# pressure-humidity-main.net
KiCad netlist of a schematic drawn in EAGLE
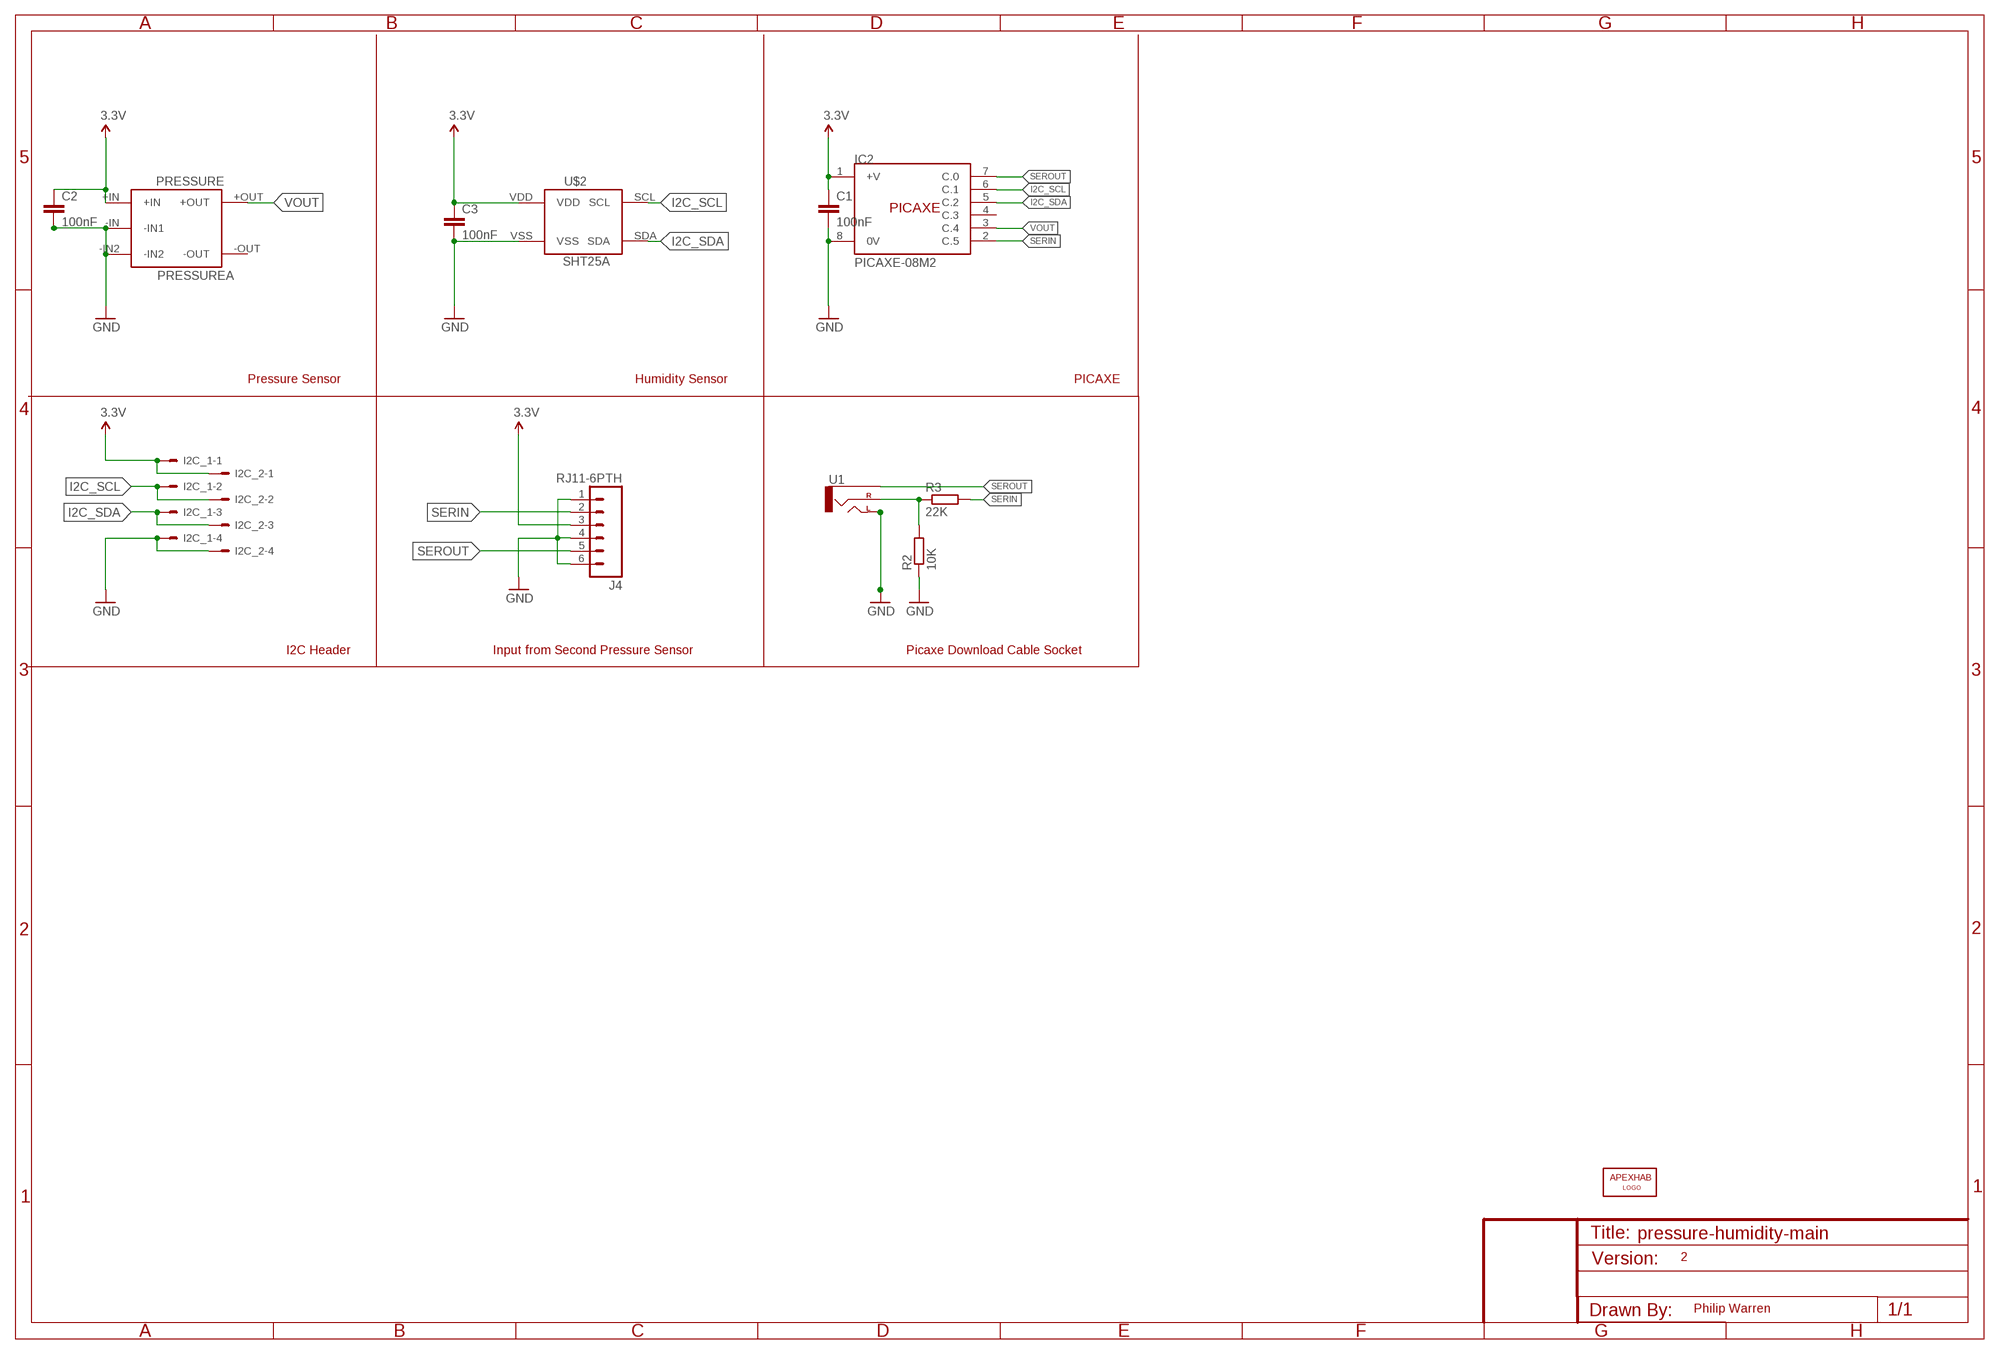
[diagram p0: schematic, sheet 1]

(export (version "E")
  (design (tool "Eeschema 10.0.6"))
  (components
    (comp (ref "C1")
      (value "100nF")
      (footprint "eagle-import:0805")
      (libsource (lib "eagle-import") (part "CAP0805"))
    )
    (comp (ref "C2")
      (value "100nF")
      (footprint "eagle-import:0805")
      (libsource (lib "eagle-import") (part "CAP0805"))
    )
    (comp (ref "C3")
      (value "100nF")
      (footprint "eagle-import:0805")
      (libsource (lib "eagle-import") (part "CAP0805"))
    )
    (comp (ref "I2C_1")
      (value "22-27-2041-04")
      (footprint "eagle-import:6410-04")
      (libsource (lib "eagle-import") (part "22-?-0427-2041"))
    )
    (comp (ref "I2C_2")
      (value "22-27-2041-04")
      (footprint "eagle-import:6410-04")
      (libsource (lib "eagle-import") (part "22-?-0427-2041"))
    )
    (comp (ref "IC2")
      (value "PICAXE-08M2")
      (footprint "eagle-import:SOIC8")
      (libsource (lib "eagle-import") (part "PICAXE-08M2"))
    )
    (comp (ref "J4")
      (value "RJ11-6PTH")
      (footprint "eagle-import:RJ11-6")
      (libsource (lib "eagle-import") (part "RJ11-6PTH"))
    )
    (comp (ref "JP1")
      (value "APEXHAB-LOGO_APEXHAB-SMALL")
      (footprint "eagle-import:APEXHAB-LOGO-SMALL")
      (libsource (lib "eagle-import") (part "APEXHAB-LOGO_APEXHAB-SMALL"))
    )
    (comp (ref "PRESSURE")
      (value "PRESSUREA")
      (footprint "eagle-import:PRESSURE")
      (libsource (lib "eagle-import") (part "PRESSUREA"))
    )
    (comp (ref "R2")
      (value "10K")
      (footprint "eagle-import:R0805")
      (libsource (lib "eagle-import") (part "R-EU_R0805"))
    )
    (comp (ref "R3")
      (value "22K")
      (footprint "eagle-import:R0805")
      (libsource (lib "eagle-import") (part "R-EU_R0805"))
    )
    (comp (ref "U$2")
      (value "SHT25A")
      (footprint "eagle-import:SHT25")
      (libsource (lib "eagle-import") (part "SHT25A"))
    )
    (comp (ref "U1")
      (value "AUDIO-JACKPTH")
      (footprint "eagle-import:AUDIO-JACK")
      (libsource (lib "eagle-import") (part "AUDIO-JACKPTH"))
    )
  )
  (nets
    (net (code "1") (name "3.3V") (class "Default")
      (node (ref "C1") (pin "1") (pinfunction "1_1") (pintype "passive"))
      (node (ref "C2") (pin "1") (pinfunction "1_1") (pintype "passive"))
      (node (ref "C3") (pin "1") (pinfunction "1_1") (pintype "passive"))
      (node (ref "I2C_1") (pin "1") (pinfunction "S_1") (pintype "passive"))
      (node (ref "I2C_2") (pin "1") (pinfunction "S_1") (pintype "passive"))
      (node (ref "IC2") (pin "1") (pinfunction "+V_1") (pintype "power_in"))
      (node (ref "J4") (pin "3") (pinfunction "3_3") (pintype "passive"))
      (node (ref "PRESSURE") (pin "+IN") (pinfunction "+IN_+IN") (pintype "bidirectional"))
      (node (ref "U$2") (pin "VDD") (pinfunction "VDD_VDD") (pintype "bidirectional"))
    )
    (net (code "2") (name "GND") (class "Default")
      (node (ref "C1") (pin "2") (pinfunction "2_2") (pintype "passive"))
      (node (ref "C2") (pin "2") (pinfunction "2_2") (pintype "passive"))
      (node (ref "C3") (pin "2") (pinfunction "2_2") (pintype "passive"))
      (node (ref "I2C_1") (pin "4") (pinfunction "S_4") (pintype "passive"))
      (node (ref "I2C_2") (pin "4") (pinfunction "S_4") (pintype "passive"))
      (node (ref "IC2") (pin "8") (pinfunction "0V_8") (pintype "power_in"))
      (node (ref "J4") (pin "1") (pinfunction "1_1") (pintype "passive"))
      (node (ref "J4") (pin "4") (pinfunction "4_4") (pintype "passive"))
      (node (ref "J4") (pin "6") (pinfunction "6_6") (pintype "passive"))
      (node (ref "PRESSURE") (pin "-IN") (pinfunction "-IN1_-IN") (pintype "bidirectional"))
      (node (ref "PRESSURE") (pin "-IN2") (pinfunction "-IN2_-IN2") (pintype "bidirectional"))
      (node (ref "R2") (pin "1") (pinfunction "1_1") (pintype "passive"))
      (node (ref "U$2") (pin "VSS") (pinfunction "VSS_VSS") (pintype "bidirectional"))
      (node (ref "U1") (pin "TIP") (pinfunction "LEFT_TIP") (pintype "bidirectional"))
    )
    (net (code "3") (name "I2C_SCL") (class "Default")
      (node (ref "I2C_1") (pin "2") (pinfunction "S_2") (pintype "passive"))
      (node (ref "I2C_2") (pin "2") (pinfunction "S_2") (pintype "passive"))
      (node (ref "IC2") (pin "6") (pinfunction "C.1_6") (pintype "bidirectional"))
      (node (ref "U$2") (pin "SCL") (pinfunction "SCL_SCL") (pintype "bidirectional"))
    )
    (net (code "4") (name "I2C_SDA") (class "Default")
      (node (ref "I2C_1") (pin "3") (pinfunction "S_3") (pintype "passive"))
      (node (ref "I2C_2") (pin "3") (pinfunction "S_3") (pintype "passive"))
      (node (ref "IC2") (pin "5") (pinfunction "C.2_5") (pintype "bidirectional"))
      (node (ref "U$2") (pin "SDA") (pinfunction "SDA_SDA") (pintype "bidirectional"))
    )
    (net (code "5") (name "Net-(U1-RIGHT)") (class "Default")
      (node (ref "R2") (pin "2") (pinfunction "2_2") (pintype "passive"))
      (node (ref "R3") (pin "1") (pinfunction "1_1") (pintype "passive"))
      (node (ref "U1") (pin "RING") (pinfunction "RIGHT_RING") (pintype "bidirectional"))
    )
    (net (code "6") (name "SERIN") (class "Default")
      (node (ref "IC2") (pin "2") (pinfunction "C.5_2") (pintype "bidirectional"))
      (node (ref "J4") (pin "2") (pinfunction "2_2") (pintype "passive"))
      (node (ref "R3") (pin "2") (pinfunction "2_2") (pintype "passive"))
    )
    (net (code "7") (name "SEROUT") (class "Default")
      (node (ref "IC2") (pin "7") (pinfunction "C.0_7") (pintype "bidirectional"))
      (node (ref "J4") (pin "5") (pinfunction "5_5") (pintype "passive"))
      (node (ref "U1") (pin "SLEEVE") (pinfunction "SLEEVE_SLEEVE") (pintype "bidirectional"))
    )
    (net (code "8") (name "VOUT") (class "Default")
      (node (ref "IC2") (pin "3") (pinfunction "C.4_3") (pintype "bidirectional"))
      (node (ref "PRESSURE") (pin "+OUT") (pinfunction "+OUT_+OUT") (pintype "bidirectional"))
    )
    (net (code "9") (name "unconnected-(IC2-C.3-Pad4)") (class "Default")
      (node (ref "IC2") (pin "4") (pinfunction "C.3_4") (pintype "bidirectional"))
    )
    (net (code "10") (name "unconnected-(PRESSURE-Pad-OUT)") (class "Default")
      (node (ref "PRESSURE") (pin "-OUT") (pinfunction "-OUT_-OUT") (pintype "bidirectional"))
    )
  )
)
